# Tritag_Color_Sensor_Board.net
KiCad netlist of a schematic drawn in EAGLE
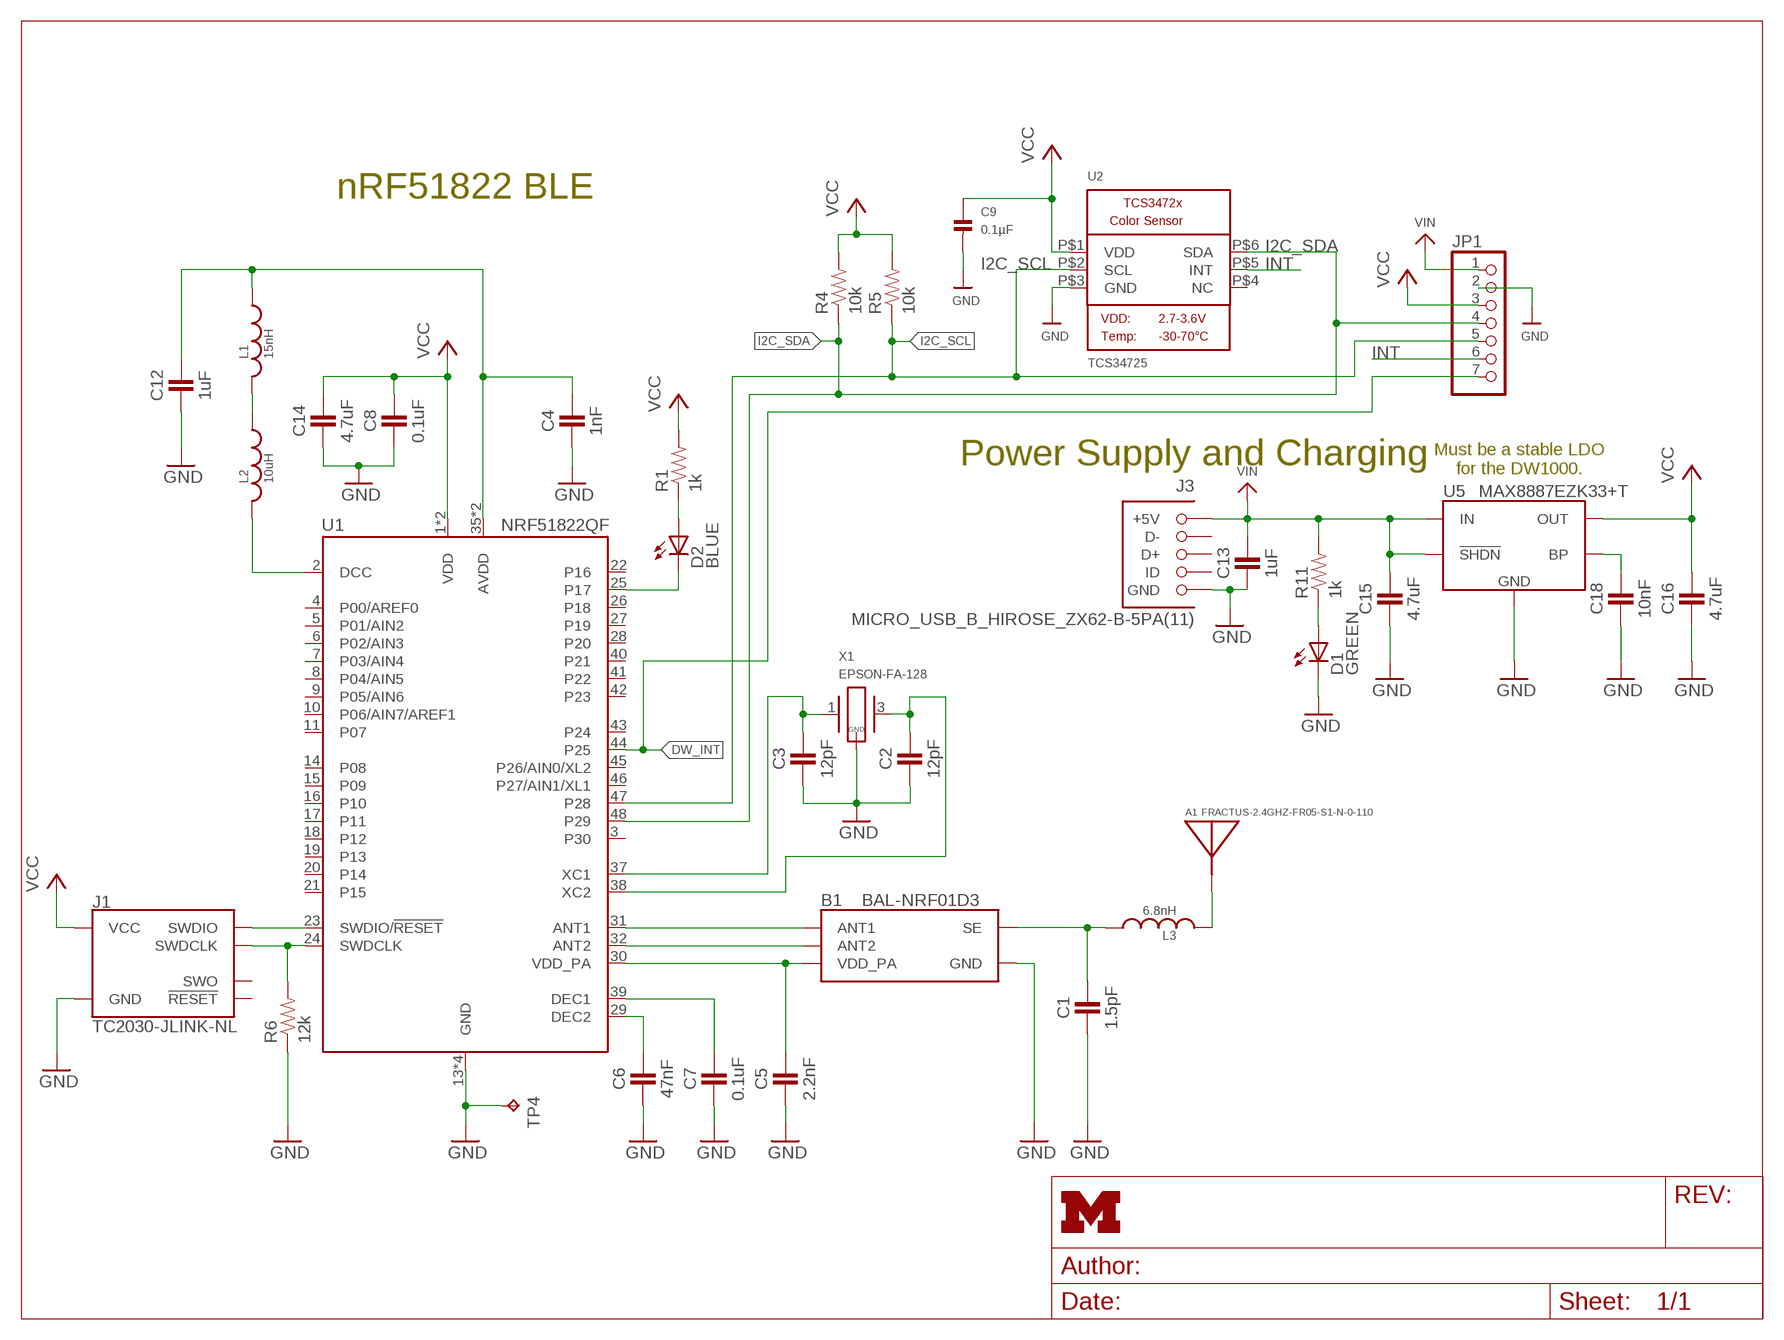
[diagram p0: schematic, sheet 1]

(export (version "E")
  (design (tool "Eeschema 10.0.6"))
  (components
    (comp (ref "A1")
      (value "FRACTUS-2.4GHZ-FR05-S1-N-0-110")
      (footprint "eagle-import:FRACTUS-ANTENNA-FR05-S1-N-0-110")
      (libsource (lib "eagle-import") (part "FRACTUS-2.4GHZ-FR05-S1-N-0-110"))
    )
    (comp (ref "B1")
      (value "BAL-NRF01D3")
      (footprint "eagle-import:BAL-NRF01D3")
      (libsource (lib "eagle-import") (part "BAL-NRF01D3"))
    )
    (comp (ref "C1")
      (value "1.5pF")
      (footprint "eagle-import:0402_CAP")
      (libsource (lib "eagle-import") (part "CAPACITOR"))
    )
    (comp (ref "C2")
      (value "12pF")
      (footprint "eagle-import:0402_CAP")
      (libsource (lib "eagle-import") (part "CAPACITOR"))
    )
    (comp (ref "C3")
      (value "12pF")
      (footprint "eagle-import:0402_CAP")
      (libsource (lib "eagle-import") (part "CAPACITOR"))
    )
    (comp (ref "C4")
      (value "1nF")
      (footprint "eagle-import:0402_CAP")
      (libsource (lib "eagle-import") (part "CAPACITOR"))
    )
    (comp (ref "C5")
      (value "2.2nF")
      (footprint "eagle-import:0402_CAP")
      (libsource (lib "eagle-import") (part "CAPACITOR"))
    )
    (comp (ref "C6")
      (value "47nF")
      (footprint "eagle-import:0402_CAP")
      (libsource (lib "eagle-import") (part "CAPACITOR"))
    )
    (comp (ref "C7")
      (value "0.1uF")
      (footprint "eagle-import:0402_CAP")
      (libsource (lib "eagle-import") (part "CAPACITOR"))
    )
    (comp (ref "C8")
      (value "0.1uF")
      (footprint "eagle-import:0402_CAP")
      (libsource (lib "eagle-import") (part "CAPACITOR"))
    )
    (comp (ref "C9")
      (value "0.1µF")
      (footprint "eagle-import:_0805")
      (libsource (lib "eagle-import") (part "CAP_CERAMIC_0805"))
    )
    (comp (ref "C12")
      (value "1uF")
      (footprint "eagle-import:0402_CAP")
      (libsource (lib "eagle-import") (part "CAPACITOR"))
    )
    (comp (ref "C13")
      (value "1uF")
      (footprint "eagle-import:0402_CAP")
      (libsource (lib "eagle-import") (part "CAPACITOR"))
    )
    (comp (ref "C14")
      (value "4.7uF")
      (footprint "eagle-import:0402_CAP")
      (libsource (lib "eagle-import") (part "CAPACITOR"))
    )
    (comp (ref "C15")
      (value "4.7uF")
      (footprint "eagle-import:0402_CAP")
      (libsource (lib "eagle-import") (part "CAPACITOR"))
    )
    (comp (ref "C16")
      (value "4.7uF")
      (footprint "eagle-import:0402_CAP")
      (libsource (lib "eagle-import") (part "CAPACITOR"))
    )
    (comp (ref "C18")
      (value "10nF")
      (footprint "eagle-import:0402_CAP")
      (libsource (lib "eagle-import") (part "CAPACITOR"))
    )
    (comp (ref "D1")
      (value "GREEN")
      (footprint "eagle-import:LED-0603")
      (libsource (lib "eagle-import") (part "LED0603"))
    )
    (comp (ref "D2")
      (value "BLUE")
      (footprint "eagle-import:LED-0603")
      (libsource (lib "eagle-import") (part "LED0603"))
    )
    (comp (ref "J1")
      (value "TC2030-JLINK-NL")
      (footprint "eagle-import:TC2030-IDC-NL")
      (libsource (lib "eagle-import") (part "TC2030-JLINK-NL"))
    )
    (comp (ref "J3")
      (value "MICRO_USB_B_HIROSE_ZX62-B-5PA(11)")
      (footprint "eagle-import:USB_MICRO_B-HIROSE-ZX62-B-5PA(11)")
      (libsource (lib "eagle-import") (part "MICRO_USB_B_HIROSE_ZX62-B-5PA(11)"))
    )
    (comp (ref "JP1")
      (value "HEADER-1X770MIL")
      (footprint "eagle-import:1X07_ROUND_70")
      (libsource (lib "eagle-import") (part "HEADER-1X770MIL"))
    )
    (comp (ref "L1")
      (value "15nH")
      (footprint "eagle-import:0402_CAP")
      (libsource (lib "eagle-import") (part "INDUCTOR0402"))
    )
    (comp (ref "L2")
      (value "10uH")
      (footprint "eagle-import:0603_CAP")
      (libsource (lib "eagle-import") (part "INDUCTOR0603"))
    )
    (comp (ref "L3")
      (value "6.8nH")
      (footprint "eagle-import:0402_CAP")
      (libsource (lib "eagle-import") (part "INDUCTOR0402"))
    )
    (comp (ref "R1")
      (value "1k")
      (footprint "eagle-import:0402_RES")
      (libsource (lib "eagle-import") (part "RESISTOR0402_RES"))
    )
    (comp (ref "R4")
      (value "10k")
      (footprint "eagle-import:0402_RES")
      (libsource (lib "eagle-import") (part "RESISTOR0402_RES"))
    )
    (comp (ref "R5")
      (value "10k")
      (footprint "eagle-import:0402_RES")
      (libsource (lib "eagle-import") (part "RESISTOR0402_RES"))
    )
    (comp (ref "R6")
      (value "12k")
      (footprint "eagle-import:0402_RES")
      (libsource (lib "eagle-import") (part "RESISTOR0402_RES"))
    )
    (comp (ref "R11")
      (value "1k")
      (footprint "eagle-import:0402_RES")
      (libsource (lib "eagle-import") (part "RESISTOR0402_RES"))
    )
    (comp (ref "TP4")
      (value "TPTP06SQ")
      (footprint "eagle-import:TP06SQ")
      (libsource (lib "eagle-import") (part "TPTP06SQ"))
    )
    (comp (ref "U1")
      (value "NRF51822QF")
      (footprint "eagle-import:QFN-48-6MM")
      (libsource (lib "eagle-import") (part "NRF51822QF"))
    )
    (comp (ref "U2")
      (value "TCS34725")
      (footprint "eagle-import:TCS3472_FN6")
      (libsource (lib "eagle-import") (part "LIGHT_TCS3472"))
    )
    (comp (ref "U5")
      (value "MAX8887EZK33+T")
      (footprint "eagle-import:SOT-23-5")
      (libsource (lib "eagle-import") (part "MAX8887EZK33+T"))
    )
    (comp (ref "X1")
      (value "EPSON-FA-128")
      (footprint "eagle-import:FA-128")
      (libsource (lib "eagle-import") (part "EPSON-FA-128"))
    )
  )
  (nets
    (net (code "1") (name "/INT") (class "Default")
      (node (ref "JP1") (pin "6") (pinfunction "6_6") (pintype "passive"))
      (node (ref "U2") (pin "P$5") (pinfunction "INT_P$5") (pintype "output"))
    )
    (net (code "2") (name "DW_INT") (class "Default")
      (node (ref "JP1") (pin "7") (pinfunction "7_7") (pintype "passive"))
      (node (ref "U1") (pin "44") (pinfunction "P25_44") (pintype "bidirectional"))
    )
    (net (code "3") (name "GND") (class "Default")
      (node (ref "B1") (pin "GND") (pinfunction "GND_GND") (pintype "bidirectional"))
      (node (ref "C1") (pin "2") (pinfunction "2_2") (pintype "bidirectional"))
      (node (ref "C12") (pin "2") (pinfunction "2_2") (pintype "bidirectional"))
      (node (ref "C13") (pin "2") (pinfunction "2_2") (pintype "bidirectional"))
      (node (ref "C14") (pin "2") (pinfunction "2_2") (pintype "bidirectional"))
      (node (ref "C15") (pin "2") (pinfunction "2_2") (pintype "bidirectional"))
      (node (ref "C16") (pin "2") (pinfunction "2_2") (pintype "bidirectional"))
      (node (ref "C18") (pin "2") (pinfunction "2_2") (pintype "bidirectional"))
      (node (ref "C2") (pin "2") (pinfunction "2_2") (pintype "bidirectional"))
      (node (ref "C3") (pin "2") (pinfunction "2_2") (pintype "bidirectional"))
      (node (ref "C4") (pin "2") (pinfunction "2_2") (pintype "bidirectional"))
      (node (ref "C5") (pin "2") (pinfunction "2_2") (pintype "bidirectional"))
      (node (ref "C6") (pin "2") (pinfunction "2_2") (pintype "bidirectional"))
      (node (ref "C7") (pin "2") (pinfunction "2_2") (pintype "bidirectional"))
      (node (ref "C8") (pin "2") (pinfunction "2_2") (pintype "bidirectional"))
      (node (ref "C9") (pin "2") (pinfunction "P$2_2") (pintype "passive"))
      (node (ref "D1") (pin "C") (pinfunction "C_C") (pintype "passive"))
      (node (ref "J1") (pin "5") (pinfunction "GND_5") (pintype "bidirectional"))
      (node (ref "J3") (pin "5") (pinfunction "GND_5") (pintype "bidirectional"))
      (node (ref "JP1") (pin "2") (pinfunction "2_2") (pintype "passive"))
      (node (ref "R6") (pin "1") (pinfunction "1_1") (pintype "passive"))
      (node (ref "TP4") (pin "TP") (pinfunction "TP_TP") (pintype "input"))
      (node (ref "U1") (pin "13") (pinfunction "GND_13") (pintype "bidirectional"))
      (node (ref "U1") (pin "33") (pinfunction "GND_33") (pintype "bidirectional"))
      (node (ref "U1") (pin "34") (pinfunction "GND_34") (pintype "bidirectional"))
      (node (ref "U1") (pin "GND") (pinfunction "GND_GND") (pintype "bidirectional"))
      (node (ref "U2") (pin "P$3") (pinfunction "GND_P$3") (pintype "power_in"))
      (node (ref "U5") (pin "2") (pinfunction "GND_2") (pintype "bidirectional"))
      (node (ref "X1") (pin "2") (pinfunction "GND_2") (pintype "bidirectional"))
      (node (ref "X1") (pin "4") (pinfunction "GND_4") (pintype "bidirectional"))
    )
    (net (code "4") (name "I2C_SCL") (class "Default")
      (node (ref "JP1") (pin "5") (pinfunction "5_5") (pintype "passive"))
      (node (ref "R5") (pin "1") (pinfunction "1_1") (pintype "passive"))
      (node (ref "U1") (pin "47") (pinfunction "P28_47") (pintype "bidirectional"))
      (node (ref "U2") (pin "P$2") (pinfunction "SCL_P$2") (pintype "bidirectional"))
    )
    (net (code "5") (name "I2C_SDA") (class "Default")
      (node (ref "JP1") (pin "4") (pinfunction "4_4") (pintype "passive"))
      (node (ref "R4") (pin "1") (pinfunction "1_1") (pintype "passive"))
      (node (ref "U1") (pin "48") (pinfunction "P29_48") (pintype "bidirectional"))
      (node (ref "U2") (pin "P$6") (pinfunction "SDA_P$6") (pintype "bidirectional"))
    )
    (net (code "6") (name "Net-(A1-ANTENNA)") (class "Default")
      (node (ref "A1") (pin "ANT") (pinfunction "ANTENNA_ANT") (pintype "bidirectional"))
      (node (ref "L3") (pin "2") (pinfunction "2_2") (pintype "bidirectional"))
    )
    (net (code "7") (name "Net-(B1-PadSE)") (class "Default")
      (node (ref "B1") (pin "SE") (pinfunction "SE_SE") (pintype "bidirectional"))
      (node (ref "C1") (pin "1") (pinfunction "1_1") (pintype "bidirectional"))
      (node (ref "L3") (pin "1") (pinfunction "1_1") (pintype "bidirectional"))
    )
    (net (code "8") (name "Net-(B1-VDD_PA)") (class "Default")
      (node (ref "B1") (pin "VCC") (pinfunction "VDD_PA_VCC") (pintype "bidirectional"))
      (node (ref "C5") (pin "1") (pinfunction "1_1") (pintype "bidirectional"))
      (node (ref "U1") (pin "30") (pinfunction "VDD_PA_30") (pintype "bidirectional"))
    )
    (net (code "9") (name "Net-(C12-Pad1)") (class "Default")
      (node (ref "C12") (pin "1") (pinfunction "1_1") (pintype "bidirectional"))
      (node (ref "C4") (pin "1") (pinfunction "1_1") (pintype "bidirectional"))
      (node (ref "L1") (pin "1") (pinfunction "1_1") (pintype "bidirectional"))
      (node (ref "U1") (pin "35") (pinfunction "AVDD_35") (pintype "bidirectional"))
      (node (ref "U1") (pin "36") (pinfunction "AVDD_36") (pintype "bidirectional"))
    )
    (net (code "10") (name "Net-(D1-PadA)") (class "Default")
      (node (ref "D1") (pin "A") (pinfunction "A_A") (pintype "passive"))
      (node (ref "R11") (pin "1") (pinfunction "1_1") (pintype "passive"))
    )
    (net (code "11") (name "Net-(D2-PadA)") (class "Default")
      (node (ref "D2") (pin "A") (pinfunction "A_A") (pintype "passive"))
      (node (ref "R1") (pin "1") (pinfunction "1_1") (pintype "passive"))
    )
    (net (code "12") (name "Net-(J1-SWDCLK)") (class "Default")
      (node (ref "J1") (pin "4") (pinfunction "SWDCLK_4") (pintype "bidirectional"))
      (node (ref "R6") (pin "2") (pinfunction "2_2") (pintype "passive"))
      (node (ref "U1") (pin "24") (pinfunction "SWDCLK_24") (pintype "bidirectional"))
    )
    (net (code "13") (name "Net-(J1-SWDIO)") (class "Default")
      (node (ref "J1") (pin "2") (pinfunction "SWDIO_2") (pintype "bidirectional"))
      (node (ref "U1") (pin "23") (pinfunction "SWDIO/~{RESET}_23") (pintype "bidirectional"))
    )
    (net (code "14") (name "Net-(L1-Pad2)") (class "Default")
      (node (ref "L1") (pin "2") (pinfunction "2_2") (pintype "bidirectional"))
      (node (ref "L2") (pin "1") (pinfunction "1_1") (pintype "bidirectional"))
    )
    (net (code "15") (name "Net-(U1-ANT1)") (class "Default")
      (node (ref "B1") (pin "ANT1") (pinfunction "ANT1_ANT1") (pintype "bidirectional"))
      (node (ref "U1") (pin "31") (pinfunction "ANT1_31") (pintype "bidirectional"))
    )
    (net (code "16") (name "Net-(U1-ANT2)") (class "Default")
      (node (ref "B1") (pin "ANT2") (pinfunction "ANT2_ANT2") (pintype "bidirectional"))
      (node (ref "U1") (pin "32") (pinfunction "ANT2_32") (pintype "bidirectional"))
    )
    (net (code "17") (name "Net-(U1-DCC)") (class "Default")
      (node (ref "L2") (pin "2") (pinfunction "2_2") (pintype "bidirectional"))
      (node (ref "U1") (pin "2") (pinfunction "DCC_2") (pintype "bidirectional"))
    )
    (net (code "18") (name "Net-(U1-DEC1)") (class "Default")
      (node (ref "C7") (pin "1") (pinfunction "1_1") (pintype "bidirectional"))
      (node (ref "U1") (pin "39") (pinfunction "DEC1_39") (pintype "bidirectional"))
    )
    (net (code "19") (name "Net-(U1-DEC2)") (class "Default")
      (node (ref "C6") (pin "1") (pinfunction "1_1") (pintype "bidirectional"))
      (node (ref "U1") (pin "29") (pinfunction "DEC2_29") (pintype "bidirectional"))
    )
    (net (code "20") (name "Net-(U1-P17)") (class "Default")
      (node (ref "D2") (pin "C") (pinfunction "C_C") (pintype "passive"))
      (node (ref "U1") (pin "25") (pinfunction "P17_25") (pintype "bidirectional"))
    )
    (net (code "21") (name "Net-(U1-XC1)") (class "Default")
      (node (ref "C3") (pin "1") (pinfunction "1_1") (pintype "bidirectional"))
      (node (ref "U1") (pin "37") (pinfunction "XC1_37") (pintype "bidirectional"))
      (node (ref "X1") (pin "1") (pinfunction "1_1") (pintype "bidirectional"))
    )
    (net (code "22") (name "Net-(U1-XC2)") (class "Default")
      (node (ref "C2") (pin "1") (pinfunction "1_1") (pintype "bidirectional"))
      (node (ref "U1") (pin "38") (pinfunction "XC2_38") (pintype "bidirectional"))
      (node (ref "X1") (pin "3") (pinfunction "2_3") (pintype "bidirectional"))
    )
    (net (code "23") (name "Net-(U5-BP)") (class "Default")
      (node (ref "C18") (pin "1") (pinfunction "1_1") (pintype "bidirectional"))
      (node (ref "U5") (pin "4") (pinfunction "BP_4") (pintype "bidirectional"))
    )
    (net (code "24") (name "VCC") (class "Default")
      (node (ref "C14") (pin "1") (pinfunction "1_1") (pintype "bidirectional"))
      (node (ref "C16") (pin "1") (pinfunction "1_1") (pintype "bidirectional"))
      (node (ref "C8") (pin "1") (pinfunction "1_1") (pintype "bidirectional"))
      (node (ref "C9") (pin "1") (pinfunction "P$1_1") (pintype "passive"))
      (node (ref "J1") (pin "1") (pinfunction "VCC_1") (pintype "bidirectional"))
      (node (ref "JP1") (pin "3") (pinfunction "3_3") (pintype "passive"))
      (node (ref "R1") (pin "2") (pinfunction "2_2") (pintype "passive"))
      (node (ref "R4") (pin "2") (pinfunction "2_2") (pintype "passive"))
      (node (ref "R5") (pin "2") (pinfunction "2_2") (pintype "passive"))
      (node (ref "U1") (pin "1") (pinfunction "VDD_1") (pintype "bidirectional"))
      (node (ref "U1") (pin "12") (pinfunction "VDD_12") (pintype "bidirectional"))
      (node (ref "U2") (pin "P$1") (pinfunction "VDD_P$1") (pintype "power_in"))
      (node (ref "U5") (pin "5") (pinfunction "OUT_5") (pintype "bidirectional"))
    )
    (net (code "25") (name "VIN") (class "Default")
      (node (ref "C13") (pin "1") (pinfunction "1_1") (pintype "bidirectional"))
      (node (ref "C15") (pin "1") (pinfunction "1_1") (pintype "bidirectional"))
      (node (ref "J3") (pin "1") (pinfunction "+5V_1") (pintype "bidirectional"))
      (node (ref "JP1") (pin "1") (pinfunction "1_1") (pintype "passive"))
      (node (ref "R11") (pin "2") (pinfunction "2_2") (pintype "passive"))
      (node (ref "U5") (pin "1") (pinfunction "IN_1") (pintype "bidirectional"))
      (node (ref "U5") (pin "3") (pinfunction "~{SHDN}_3") (pintype "bidirectional"))
    )
    (net (code "26") (name "unconnected-(J1-SWO-Pad6)") (class "Default")
      (node (ref "J1") (pin "6") (pinfunction "SWO_6") (pintype "bidirectional"))
    )
    (net (code "27") (name "unconnected-(J1-~{RESET}-Pad3)") (class "Default")
      (node (ref "J1") (pin "3") (pinfunction "~{RESET}_3") (pintype "bidirectional"))
    )
    (net (code "28") (name "unconnected-(J3-D+-Pad3)") (class "Default")
      (node (ref "J3") (pin "3") (pinfunction "D+_3") (pintype "bidirectional"))
    )
    (net (code "29") (name "unconnected-(J3-D--Pad2)") (class "Default")
      (node (ref "J3") (pin "2") (pinfunction "D-_2") (pintype "bidirectional"))
    )
    (net (code "30") (name "unconnected-(J3-ID-Pad4)") (class "Default")
      (node (ref "J3") (pin "4") (pinfunction "ID_4") (pintype "bidirectional"))
    )
    (net (code "31") (name "unconnected-(U1-P00{slash}AREF0-Pad4)") (class "Default")
      (node (ref "U1") (pin "4") (pinfunction "P00/AREF0_4") (pintype "bidirectional"))
    )
    (net (code "32") (name "unconnected-(U1-P01{slash}AIN2-Pad5)") (class "Default")
      (node (ref "U1") (pin "5") (pinfunction "P01/AIN2_5") (pintype "bidirectional"))
    )
    (net (code "33") (name "unconnected-(U1-P02{slash}AIN3-Pad6)") (class "Default")
      (node (ref "U1") (pin "6") (pinfunction "P02/AIN3_6") (pintype "bidirectional"))
    )
    (net (code "34") (name "unconnected-(U1-P03{slash}AIN4-Pad7)") (class "Default")
      (node (ref "U1") (pin "7") (pinfunction "P03/AIN4_7") (pintype "bidirectional"))
    )
    (net (code "35") (name "unconnected-(U1-P04{slash}AIN5-Pad8)") (class "Default")
      (node (ref "U1") (pin "8") (pinfunction "P04/AIN5_8") (pintype "bidirectional"))
    )
    (net (code "36") (name "unconnected-(U1-P05{slash}AIN6-Pad9)") (class "Default")
      (node (ref "U1") (pin "9") (pinfunction "P05/AIN6_9") (pintype "bidirectional"))
    )
    (net (code "37") (name "unconnected-(U1-P06{slash}AIN7{slash}AREF1-Pad10)") (class "Default")
      (node (ref "U1") (pin "10") (pinfunction "P06/AIN7/AREF1_10") (pintype "bidirectional"))
    )
    (net (code "38") (name "unconnected-(U1-P07-Pad11)") (class "Default")
      (node (ref "U1") (pin "11") (pinfunction "P07_11") (pintype "bidirectional"))
    )
    (net (code "39") (name "unconnected-(U1-P08-Pad14)") (class "Default")
      (node (ref "U1") (pin "14") (pinfunction "P08_14") (pintype "bidirectional"))
    )
    (net (code "40") (name "unconnected-(U1-P09-Pad15)") (class "Default")
      (node (ref "U1") (pin "15") (pinfunction "P09_15") (pintype "bidirectional"))
    )
    (net (code "41") (name "unconnected-(U1-P10-Pad16)") (class "Default")
      (node (ref "U1") (pin "16") (pinfunction "P10_16") (pintype "bidirectional"))
    )
    (net (code "42") (name "unconnected-(U1-P11-Pad17)") (class "Default")
      (node (ref "U1") (pin "17") (pinfunction "P11_17") (pintype "bidirectional"))
    )
    (net (code "43") (name "unconnected-(U1-P12-Pad18)") (class "Default")
      (node (ref "U1") (pin "18") (pinfunction "P12_18") (pintype "bidirectional"))
    )
    (net (code "44") (name "unconnected-(U1-P13-Pad19)") (class "Default")
      (node (ref "U1") (pin "19") (pinfunction "P13_19") (pintype "bidirectional"))
    )
    (net (code "45") (name "unconnected-(U1-P14-Pad20)") (class "Default")
      (node (ref "U1") (pin "20") (pinfunction "P14_20") (pintype "bidirectional"))
    )
    (net (code "46") (name "unconnected-(U1-P15-Pad21)") (class "Default")
      (node (ref "U1") (pin "21") (pinfunction "P15_21") (pintype "bidirectional"))
    )
    (net (code "47") (name "unconnected-(U1-P16-Pad22)") (class "Default")
      (node (ref "U1") (pin "22") (pinfunction "P16_22") (pintype "bidirectional"))
    )
    (net (code "48") (name "unconnected-(U1-P18-Pad26)") (class "Default")
      (node (ref "U1") (pin "26") (pinfunction "P18_26") (pintype "bidirectional"))
    )
    (net (code "49") (name "unconnected-(U1-P19-Pad27)") (class "Default")
      (node (ref "U1") (pin "27") (pinfunction "P19_27") (pintype "bidirectional"))
    )
    (net (code "50") (name "unconnected-(U1-P20-Pad28)") (class "Default")
      (node (ref "U1") (pin "28") (pinfunction "P20_28") (pintype "bidirectional"))
    )
    (net (code "51") (name "unconnected-(U1-P21-Pad40)") (class "Default")
      (node (ref "U1") (pin "40") (pinfunction "P21_40") (pintype "bidirectional"))
    )
    (net (code "52") (name "unconnected-(U1-P22-Pad41)") (class "Default")
      (node (ref "U1") (pin "41") (pinfunction "P22_41") (pintype "bidirectional"))
    )
    (net (code "53") (name "unconnected-(U1-P23-Pad42)") (class "Default")
      (node (ref "U1") (pin "42") (pinfunction "P23_42") (pintype "bidirectional"))
    )
    (net (code "54") (name "unconnected-(U1-P24-Pad43)") (class "Default")
      (node (ref "U1") (pin "43") (pinfunction "P24_43") (pintype "bidirectional"))
    )
    (net (code "55") (name "unconnected-(U1-P26{slash}AIN0{slash}XL2-Pad45)") (class "Default")
      (node (ref "U1") (pin "45") (pinfunction "P26/AIN0/XL2_45") (pintype "bidirectional"))
    )
    (net (code "56") (name "unconnected-(U1-P27{slash}AIN1{slash}XL1-Pad46)") (class "Default")
      (node (ref "U1") (pin "46") (pinfunction "P27/AIN1/XL1_46") (pintype "bidirectional"))
    )
    (net (code "57") (name "unconnected-(U1-P30-Pad3)") (class "Default")
      (node (ref "U1") (pin "3") (pinfunction "P30_3") (pintype "bidirectional"))
    )
    (net (code "58") (name "unconnected-(U2-NC-PadP$4)") (class "Default")
      (node (ref "U2") (pin "P$4") (pinfunction "NC_P$4") (pintype "no_connect"))
    )
  )
)
